# esp8266.net
KiCad netlist of a schematic drawn in Altium Designer
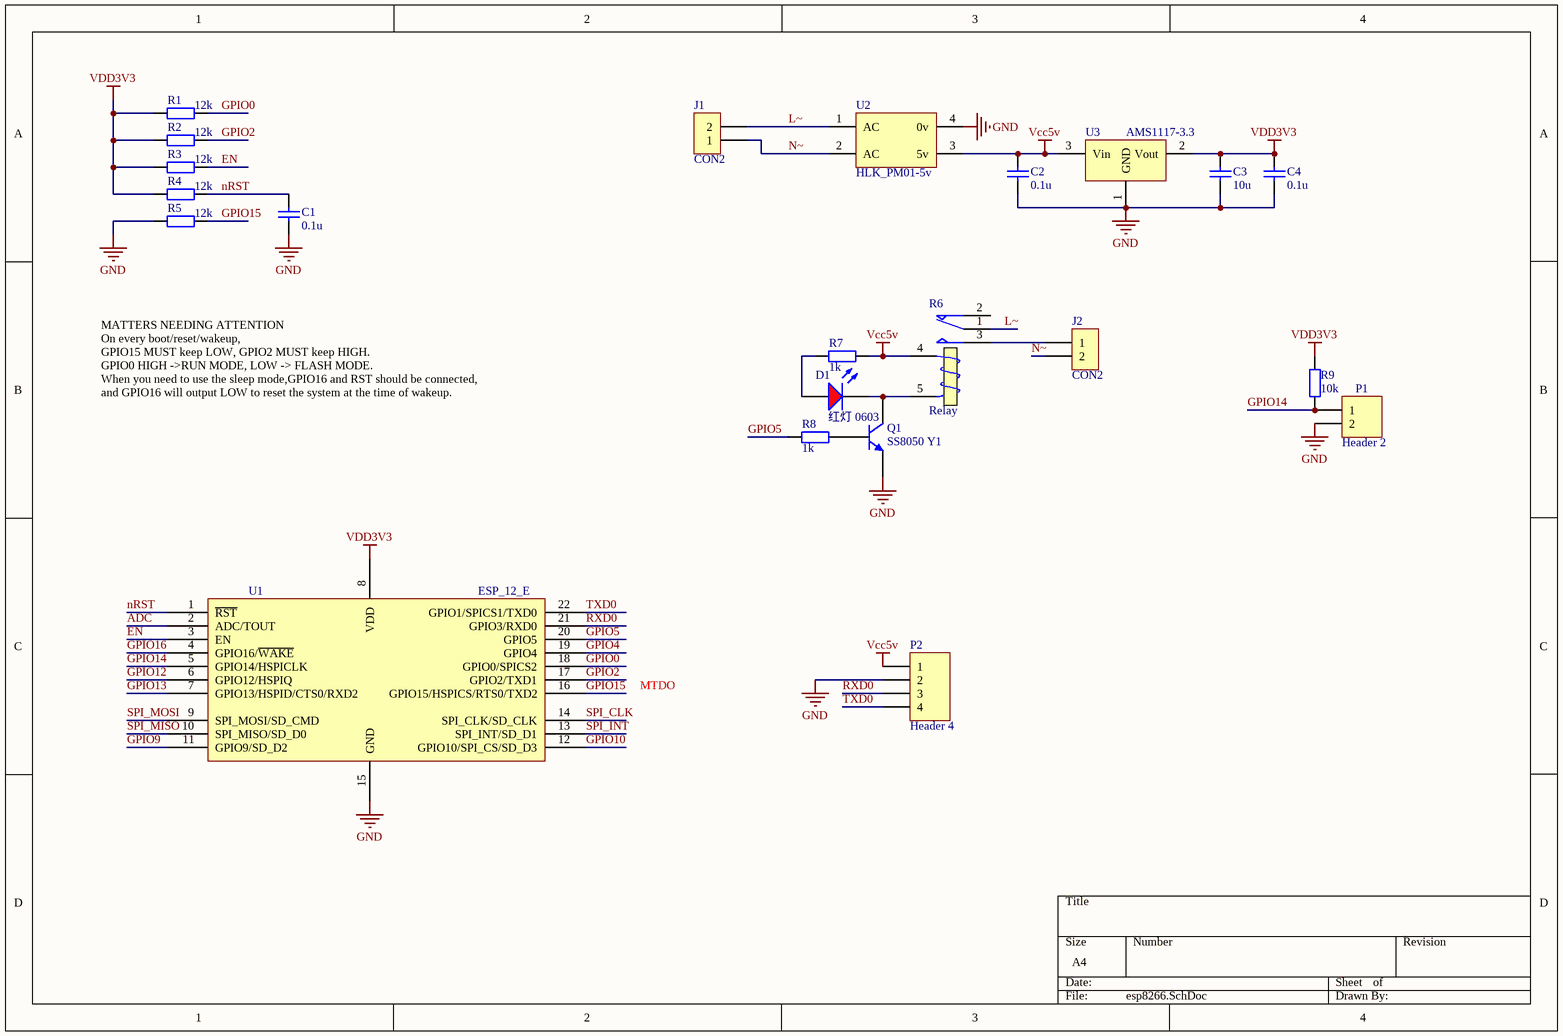
[diagram p0: esp8266.SchDoc]

(export (version "E")
  (design (tool "Eeschema 10.0.6"))
  (components
    (comp (ref "C1") (value "0.1u") (footprint "C0603") (libsource (lib "library") (part "Cap_0402")))
    (comp (ref "C2") (value "0.1u") (footprint "C0603") (libsource (lib "library") (part "Cap_0402")))
    (comp (ref "C3") (value "10u") (footprint "C0603") (libsource (lib "library") (part "Cap_0402")))
    (comp (ref "C4") (value "0.1u") (footprint "C0603") (libsource (lib "library") (part "Cap_0402")))
    (comp (ref "D1")
      (value "红灯 0603")
      (footprint "0603_LED_S1")
      (description "发光二极管")
      (libsource (lib "library") (part "0603 红灯"))
    )
    (comp (ref "J1")
      (value "CON2")
      (footprint "CON_5.08_2")
      (description "Connector")
      (libsource (lib "library") (part "CON2"))
    )
    (comp (ref "J2")
      (value "CON2")
      (footprint "CON_5.08_2")
      (description "Connector")
      (libsource (lib "") (part "CON2_1"))
    )
    (comp (ref "P1")
      (value "Header 2")
      (footprint "HDR1X2")
      (description "Header, 2-Pin")
      (fields (field (name "PUBLISHER") "Altium Limited"))
      (libsource (lib "library") (part "Header 2"))
    )
    (comp (ref "P2")
      (value "Header 4")
      (footprint "HDR1X4")
      (description "Header, 4-Pin")
      (fields (field (name "PUBLISHER") "Altium Limited"))
      (libsource (lib "library") (part "Header 4"))
    )
    (comp (ref "Q1")
      (value "SS8050 Y1")
      (footprint "SOT-23(SOT-23-3)")
      (description "三极管")
      (libsource (lib "library") (part "SOT-23 SS8050 Y1"))
    )
    (comp (ref "R1") (value "12k") (footprint "R0603") (libsource (lib "") (part "Res_0402_1")))
    (comp (ref "R2") (value "12k") (footprint "R0603") (libsource (lib "") (part "Res_0402_1")))
    (comp (ref "R3") (value "12k") (footprint "R0603") (libsource (lib "") (part "Res_0402_1")))
    (comp (ref "R4") (value "12k") (footprint "R0603") (libsource (lib "") (part "Res_0402_1")))
    (comp (ref "R5") (value "12k") (footprint "R0603") (libsource (lib "") (part "Res_0402_1")))
    (comp (ref "R6")
      (value "Relay")
      (footprint "HF3FF-JQC-3FF-005")
      (libsource (lib "library") (part "Relay"))
    )
    (comp (ref "R7") (value "1k") (footprint "R0603") (libsource (lib "") (part "Res_0402_1")))
    (comp (ref "R8") (value "1k") (footprint "R0603") (libsource (lib "") (part "Res_0402_1")))
    (comp (ref "R9") (value "10k") (footprint "R0603") (libsource (lib "library") (part "Res_0402")))
    (comp (ref "U1")
      (value "ESP_12_E")
      (footprint "ESP8266")
      (description "ESP-12 Wi-Fi Module by AI-Thinker")
      (libsource (lib "library") (part "ESP_12_E"))
    )
    (comp (ref "U2")
      (value "HLK_PM01-5v")
      (footprint "HLK_PM01-5v")
      (libsource (lib "library") (part "HLK_PM01-5v"))
    )
    (comp (ref "U3") (value "AMS1117-3.3") (footprint "AMS1117") (libsource (lib "library") (part "AMS1117")))
  )
  (nets
    (net (code "1") (name "/ADC") (class "Default")
      (node (ref "U1") (pin "2") (pinfunction "ADC/TOUT_2") (pintype "passive"))
    )
    (net (code "2") (name "/EN") (class "Default")
      (node (ref "R3") (pin "2") (pinfunction "2_2") (pintype "passive"))
      (node (ref "U1") (pin "3") (pinfunction "EN_3") (pintype "passive"))
    )
    (net (code "3") (name "/GPIO0") (class "Default")
      (node (ref "R1") (pin "2") (pinfunction "2_2") (pintype "passive"))
      (node (ref "U1") (pin "18") (pinfunction "GPIO0/SPICS2_18") (pintype "passive"))
    )
    (net (code "4") (name "/GPIO2") (class "Default")
      (node (ref "R2") (pin "2") (pinfunction "2_2") (pintype "passive"))
      (node (ref "U1") (pin "17") (pinfunction "GPIO2/TXD1_17") (pintype "passive"))
    )
    (net (code "5") (name "/GPIO4") (class "Default")
      (node (ref "U1") (pin "19") (pinfunction "GPIO4_19") (pintype "passive"))
    )
    (net (code "6") (name "/GPIO5") (class "Default")
      (node (ref "R8") (pin "1") (pinfunction "1_1") (pintype "passive"))
      (node (ref "U1") (pin "20") (pinfunction "GPIO5_20") (pintype "passive"))
    )
    (net (code "7") (name "/GPIO9") (class "Default")
      (node (ref "U1") (pin "11") (pinfunction "GPIO9/SD_D2_11") (pintype "passive"))
    )
    (net (code "8") (name "/GPIO10") (class "Default")
      (node (ref "U1") (pin "12") (pinfunction "GPIO10/SPI_CS/SD_D3_12") (pintype "passive"))
    )
    (net (code "9") (name "/GPIO12") (class "Default")
      (node (ref "U1") (pin "6") (pinfunction "GPIO12/HSPIQ_6") (pintype "passive"))
    )
    (net (code "10") (name "/GPIO13") (class "Default")
      (node (ref "U1") (pin "7") (pinfunction "GPIO13/HSPID/CTS0/RXD2_7") (pintype "passive"))
    )
    (net (code "11") (name "/GPIO14") (class "Default")
      (node (ref "P1") (pin "1") (pinfunction "1_1") (pintype "passive"))
      (node (ref "R9") (pin "1") (pinfunction "1_1") (pintype "passive"))
      (node (ref "U1") (pin "5") (pinfunction "GPIO14/HSPICLK_5") (pintype "passive"))
    )
    (net (code "12") (name "/GPIO15") (class "Default")
      (node (ref "R5") (pin "2") (pinfunction "2_2") (pintype "passive"))
      (node (ref "U1") (pin "16") (pinfunction "GPIO15/HSPICS/RTS0/TXD2_16") (pintype "passive"))
    )
    (net (code "13") (name "/GPIO16") (class "Default")
      (node (ref "U1") (pin "4") (pinfunction "GPIO16/~{WAKE}_4") (pintype "passive"))
    )
    (net (code "14") (name "/L~") (class "Default")
      (node (ref "J1") (pin "2") (pinfunction "2_2") (pintype "passive"))
      (node (ref "R6") (pin "1") (pinfunction "COM_1") (pintype "passive"))
      (node (ref "U2") (pin "1") (pinfunction "AC_1") (pintype "passive"))
    )
    (net (code "15") (name "/N~") (class "Default")
      (node (ref "J1") (pin "1") (pinfunction "1_1") (pintype "passive"))
      (node (ref "J2") (pin "2") (pinfunction "2_2") (pintype "passive"))
      (node (ref "U2") (pin "2") (pinfunction "AC_2") (pintype "passive"))
    )
    (net (code "16") (name "/RXD0") (class "Default")
      (node (ref "P2") (pin "3") (pinfunction "3_3") (pintype "passive"))
      (node (ref "U1") (pin "21") (pinfunction "GPIO3/RXD0_21") (pintype "passive"))
    )
    (net (code "17") (name "/SPI_CLK") (class "Default")
      (node (ref "U1") (pin "14") (pinfunction "SPI_CLK/SD_CLK_14") (pintype "passive"))
    )
    (net (code "18") (name "/SPI_INT") (class "Default")
      (node (ref "U1") (pin "13") (pinfunction "SPI_INT/SD_D1_13") (pintype "passive"))
    )
    (net (code "19") (name "/SPI_MISO") (class "Default")
      (node (ref "U1") (pin "10") (pinfunction "SPI_MISO/SD_D0_10") (pintype "passive"))
    )
    (net (code "20") (name "/SPI_MOSI") (class "Default")
      (node (ref "U1") (pin "9") (pinfunction "SPI_MOSI/SD_CMD_9") (pintype "passive"))
    )
    (net (code "21") (name "/TXD0") (class "Default")
      (node (ref "P2") (pin "4") (pinfunction "4_4") (pintype "passive"))
      (node (ref "U1") (pin "22") (pinfunction "GPIO1/SPICS1/TXD0_22") (pintype "passive"))
    )
    (net (code "22") (name "/nRST") (class "Default")
      (node (ref "C1") (pin "2") (pinfunction "2_2") (pintype "passive"))
      (node (ref "R4") (pin "2") (pinfunction "2_2") (pintype "passive"))
      (node (ref "U1") (pin "1") (pinfunction "~{RST}_1") (pintype "passive"))
    )
    (net (code "23") (name "GND") (class "Default")
      (node (ref "C1") (pin "1") (pinfunction "1_1") (pintype "passive"))
      (node (ref "C2") (pin "1") (pinfunction "1_1") (pintype "passive"))
      (node (ref "C3") (pin "1") (pinfunction "1_1") (pintype "passive"))
      (node (ref "C4") (pin "1") (pinfunction "1_1") (pintype "passive"))
      (node (ref "P1") (pin "2") (pinfunction "2_2") (pintype "passive"))
      (node (ref "P2") (pin "2") (pinfunction "2_2") (pintype "passive"))
      (node (ref "Q1") (pin "2") (pinfunction "E_2") (pintype "passive"))
      (node (ref "R5") (pin "1") (pinfunction "1_1") (pintype "passive"))
      (node (ref "U1") (pin "15") (pinfunction "GND_15") (pintype "passive"))
      (node (ref "U2") (pin "4") (pinfunction "0v_4") (pintype "passive"))
      (node (ref "U3") (pin "1") (pinfunction "GND_1") (pintype "passive"))
    )
    (net (code "24") (name "Net-(D1-PadA)") (class "Default")
      (node (ref "D1") (pin "A") (pinfunction "A_A") (pintype "passive"))
      (node (ref "R7") (pin "1") (pinfunction "1_1") (pintype "passive"))
    )
    (net (code "25") (name "Net-(Q1-B)") (class "Default")
      (node (ref "Q1") (pin "1") (pinfunction "B_1") (pintype "passive"))
      (node (ref "R8") (pin "2") (pinfunction "2_2") (pintype "passive"))
    )
    (net (code "26") (name "Net-(Q1-C)") (class "Default")
      (node (ref "D1") (pin "K") (pinfunction "K_K") (pintype "passive"))
      (node (ref "Q1") (pin "3") (pinfunction "C_3") (pintype "passive"))
      (node (ref "R6") (pin "5") (pinfunction "T2_5") (pintype "passive"))
    )
    (net (code "27") (name "Net-(R6-NO)") (class "Default")
      (node (ref "J2") (pin "1") (pinfunction "1_1") (pintype "passive"))
      (node (ref "R6") (pin "3") (pinfunction "NO_3") (pintype "passive"))
    )
    (net (code "28") (name "VDD3V3") (class "Default")
      (node (ref "C3") (pin "2") (pinfunction "2_2") (pintype "passive"))
      (node (ref "C4") (pin "2") (pinfunction "2_2") (pintype "passive"))
      (node (ref "R1") (pin "1") (pinfunction "1_1") (pintype "passive"))
      (node (ref "R2") (pin "1") (pinfunction "1_1") (pintype "passive"))
      (node (ref "R3") (pin "1") (pinfunction "1_1") (pintype "passive"))
      (node (ref "R4") (pin "1") (pinfunction "1_1") (pintype "passive"))
      (node (ref "R9") (pin "2") (pinfunction "2_2") (pintype "passive"))
      (node (ref "U1") (pin "8") (pinfunction "VDD_8") (pintype "passive"))
      (node (ref "U3") (pin "2") (pinfunction "Vout_2") (pintype "passive"))
    )
    (net (code "29") (name "Vcc5v") (class "Default")
      (node (ref "C2") (pin "2") (pinfunction "2_2") (pintype "passive"))
      (node (ref "P2") (pin "1") (pinfunction "1_1") (pintype "passive"))
      (node (ref "R6") (pin "4") (pinfunction "T1_4") (pintype "passive"))
      (node (ref "R7") (pin "2") (pinfunction "2_2") (pintype "passive"))
      (node (ref "U2") (pin "3") (pinfunction "5v_3") (pintype "passive"))
      (node (ref "U3") (pin "3") (pinfunction "Vin_3") (pintype "passive"))
    )
    (net (code "30") (name "unconnected-(R6-NC-Pad2)") (class "Default")
      (node (ref "R6") (pin "2") (pinfunction "NC_2") (pintype "passive"))
    )
  )
)
